# 48-17V_Buck_Converter.net
KiCad netlist of a schematic drawn in Altium Designer
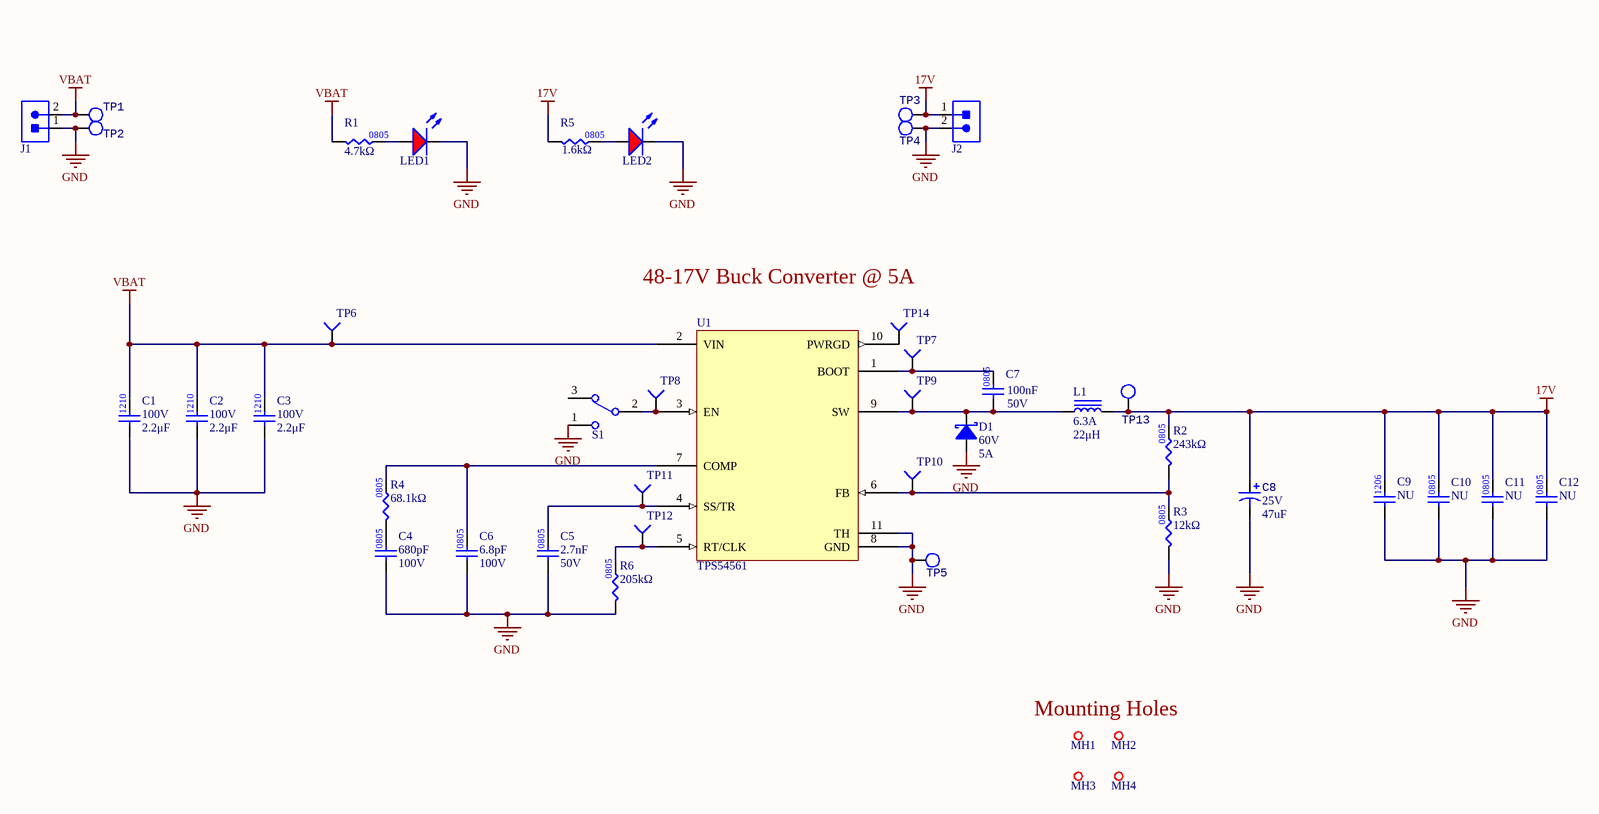
[diagram p0: 48-17V Buck Converter.SchDoc]

(export (version "E")
  (design (tool "Eeschema 10.0.6"))
  (components
    (comp (ref "C1")
      (value "2.2μF")
      (footprint "CAPC3225X270N")
      (description "CAP CER 2.2UF 100V X7R 1210")
      (fields (field (name "VOLTAGE RATING") "100V") (field (name "Comment") "CAP_2.2uF_100V_1210_1"))
      (libsource (lib "UWRT_Schematic_Library_2020") (part "CAP_2.2uF_100V_1210_1"))
    )
    (comp (ref "C2")
      (value "2.2μF")
      (footprint "CAPC3225X270N")
      (description "CAP CER 2.2UF 100V X7R 1210")
      (fields (field (name "VOLTAGE RATING") "100V") (field (name "Comment") "CAP_2.2uF_100V_1210_1"))
      (libsource (lib "UWRT_Schematic_Library_2020") (part "CAP_2.2uF_100V_1210_1"))
    )
    (comp (ref "C3")
      (value "2.2μF")
      (footprint "CAPC3225X270N")
      (description "CAP CER 2.2UF 100V X7R 1210")
      (fields (field (name "VOLTAGE RATING") "100V") (field (name "Comment") "CAP_2.2uF_100V_1210_1"))
      (libsource (lib "UWRT_Schematic_Library_2020") (part "CAP_2.2uF_100V_1210_1"))
    )
    (comp (ref "C4")
      (value "680pF")
      (footprint "CAP0805")
      (description "CAP CER 680PF 100V C0G/NP0 0805")
      (fields (field (name "VOLTAGE RATING") "100V") (field (name "Comment") "CAP_680pF_50V_0805"))
      (libsource (lib "UWRT_Schematic_Library_2020") (part "CAP_680pF_50V_0805"))
    )
    (comp (ref "C5")
      (value "2.7nF")
      (footprint "CAP0805")
      (description "CAP CER 2700PF 50V C0G 0805")
      (fields (field (name "VOLTAGE RATING") "50V") (field (name "Comment") "CAP_2.7nF_50V_0805"))
      (libsource (lib "UWRT_Schematic_Library_2020") (part "CAP_2.7nF_50V_0805"))
    )
    (comp (ref "C6")
      (value "6.8pF")
      (footprint "CAP0805")
      (description "CAP CER 6.8PF 100V C0G/NP0 0805")
      (fields (field (name "VOLTAGE RATING") "100V") (field (name "Comment") "CAP_6.8pF_100V_0805"))
      (libsource (lib "UWRT_Schematic_Library_2020") (part "CAP_6.8pF_100V_0805"))
    )
    (comp (ref "C7")
      (value "100nF")
      (footprint "CAP0805")
      (description "CAP CER 0.1UF 50V X7R 0805")
      (fields (field (name "VOLTAGE RATING") "50V") (field (name "Comment") "CAP_100nF_50V_0805"))
      (libsource (lib "UWRT_Schematic_Library_2020") (part "CAP_100nF_50V_0805"))
    )
    (comp (ref "C8")
      (value "47uF")
      (footprint "CAP_47uF_25V_ALUM")
      (description "CAP ALUM POLY 47UF 20% 25V SMD")
      (fields (field (name "VOLTAGE") "25V") (field (name "Comment") "CAP_47uF_25V_ALUM"))
      (libsource (lib "UWRT_Schematic_Library_2020") (part "CAP_47uF_25V_ALUM"))
    )
    (comp (ref "C9")
      (value "NU")
      (footprint "CAP1206")
      (description "PLACEHOLDER CAPACITOR")
      (fields (field (name "Comment") "CAP_NU_1206"))
      (libsource (lib "UWRT_Schematic_Library_2020") (part "CAP_NU_1206"))
    )
    (comp (ref "C10")
      (value "NU")
      (footprint "CAP0805")
      (description "PLACEHOLDER CAPACITOR")
      (fields (field (name "Comment") "CAP_NU_0805"))
      (libsource (lib "UWRT_Schematic_Library_2020") (part "CAP_NU_0805"))
    )
    (comp (ref "C11")
      (value "NU")
      (footprint "CAP0805")
      (description "PLACEHOLDER CAPACITOR")
      (fields (field (name "Comment") "CAP_NU_0805"))
      (libsource (lib "UWRT_Schematic_Library_2020") (part "CAP_NU_0805"))
    )
    (comp (ref "C12")
      (value "NU")
      (footprint "CAP0805")
      (description "PLACEHOLDER CAPACITOR")
      (fields (field (name "Comment") "CAP_NU_0805"))
      (libsource (lib "UWRT_Schematic_Library_2020") (part "CAP_NU_0805"))
    )
    (comp (ref "D1")
      (value "DIO_SCHOTTKY_30V_800mA")
      (footprint "SOD-323_UNIDIR")
      (description "DIODE SCHOTTKY 60V 5A SMC")
      (fields (field (name "VR (MAX)") "60V") (field (name "IO") "5A"))
      (libsource (lib "UWRT_Schematic_Library_2020") (part "DIO_SCHOTTKY_60V_5A"))
    )
    (comp (ref "J1")
      (value "CON_2POS_SCREW_TERM")
      (footprint "1935161")
      (description "TERM BLK 2POS SIDE ENTRY 5MM")
      (libsource (lib "") (part "CON_2POS_SCREW_TERM_1"))
    )
    (comp (ref "J2")
      (value "CON_2POS_SCREW_TERM")
      (footprint "1935161")
      (description "TERM BLK 2POS SIDE ENTRY 5MM")
      (libsource (lib "UWRT_Schematic_Library_2020") (part "CON_2POS_SCREW_TERM"))
    )
    (comp (ref "L1")
      (value "IND_22uH_6.3A")
      (footprint "UWRT_Footprint_Library_2020:IND_22uH_6.3A")
      (description "FIXED IND 22UH 6.3A 25.7MOHM SMD")
      (fields (field (name "CURRENT RATING") "6.3A") (field (name "INDUCTANCE") "22μH"))
      (libsource (lib "UWRT_Schematic_Library_2020") (part "IND_22uH_6.3A"))
    )
    (comp (ref "LED1")
      (value "LED_RED")
      (footprint "LED_0805_RED")
      (description "LED RED DIFFUSED 0805 SMD")
      (libsource (lib "UWRT_Schematic_Library_2020") (part "LED_RED"))
    )
    (comp (ref "LED2")
      (value "LED_RED")
      (footprint "LED_0805_RED")
      (description "LED RED DIFFUSED 0805 SMD")
      (libsource (lib "UWRT_Schematic_Library_2020") (part "LED_RED"))
    )
    (comp (ref "MH1")
      (value "MOUNTING_HOLE_M3_GIMBAL_REV2")
      (footprint "MOUNTING_HOLE_3mm_GIMBAL_REV2")
      (description "MOUNTING_HOLE_M3 Gimbal Rev2")
      (libsource (lib "UWRT_Schematic_Library_2020") (part "MOUNTING_HOLE_M3_GIMBAL_REV2"))
    )
    (comp (ref "MH2")
      (value "MOUNTING_HOLE_M3_GIMBAL_REV2")
      (footprint "MOUNTING_HOLE_3mm_GIMBAL_REV2")
      (description "MOUNTING_HOLE_M3 Gimbal Rev2")
      (libsource (lib "UWRT_Schematic_Library_2020") (part "MOUNTING_HOLE_M3_GIMBAL_REV2"))
    )
    (comp (ref "MH3")
      (value "MOUNTING_HOLE_M3_GIMBAL_REV2")
      (footprint "MOUNTING_HOLE_3mm_GIMBAL_REV2")
      (description "MOUNTING_HOLE_M3 Gimbal Rev2")
      (libsource (lib "UWRT_Schematic_Library_2020") (part "MOUNTING_HOLE_M3_GIMBAL_REV2"))
    )
    (comp (ref "MH4")
      (value "MOUNTING_HOLE_M3_GIMBAL_REV2")
      (footprint "MOUNTING_HOLE_3mm_GIMBAL_REV2")
      (description "MOUNTING_HOLE_M3 Gimbal Rev2")
      (libsource (lib "UWRT_Schematic_Library_2020") (part "MOUNTING_HOLE_M3_GIMBAL_REV2"))
    )
    (comp (ref "R1")
      (value "4.7kΩ")
      (footprint "RES0805")
      (description "RES 4.7K OHM 5% 1/8W 0805")
      (fields (field (name "LCSC PART #") "C17673") (field (name "Comment") "RES_4.7kΩ_0805_5%"))
      (libsource (lib "UWRT_Schematic_Library_2020") (part "RES_4.7kΩ_0805_5%"))
    )
    (comp (ref "R2")
      (value "243kΩ")
      (footprint "RES0805")
      (description "RES 243K OHM 1% 1/8W 0805")
      (fields (field (name "Comment") "RES_243kΩ_0805_1%_1"))
      (libsource (lib "UWRT_Schematic_Library_2020") (part "RES_243kΩ_0805_1%_1"))
    )
    (comp (ref "R3")
      (value "12kΩ")
      (footprint "RES0805")
      (description "RES 12K OHM 1% 1/8W 0805")
      (fields (field (name "Comment") "RES_12kΩ_0805_1%"))
      (libsource (lib "UWRT_Schematic_Library_2020") (part "RES_12kΩ_0805_1%"))
    )
    (comp (ref "R4")
      (value "68.1kΩ")
      (footprint "RES0805")
      (description "RES 68.1K OHM 1% 1/8W 0805")
      (fields (field (name "Comment") "RES_68.1kΩ_0805_1%"))
      (libsource (lib "UWRT_Schematic_Library_2020") (part "RES_68.1kΩ_0805_1%"))
    )
    (comp (ref "R5")
      (value "1.6kΩ")
      (footprint "RES0805")
      (description "RES 1.6K OHM 0.1% 1/4W 0805")
      (fields (field (name "TOLERANCE") "0.1%") (field (name "Comment") "RES_1.6kΩ_0805_0.1%"))
      (libsource (lib "UWRT_Schematic_Library_2020") (part "RES_1.6kΩ_0805_0.1%"))
    )
    (comp (ref "R6")
      (value "205kΩ")
      (footprint "RES0805")
      (description "RES 205K OHM 1% 1/8W 0805")
      (fields (field (name "Comment") "RES_205kΩ_0805_1%"))
      (libsource (lib "UWRT_Schematic_Library_2020") (part "RES_205kΩ_0805_1%"))
    )
    (comp (ref "S1")
      (value "SW_SLIDE_TOGGLE")
      (footprint "UWRT_Footprint_Library_2020:SW_SLIDE_TOGGLE")
      (description "SWITCH SLIDE SPDT 200MA 30V")
      (libsource (lib "UWRT_Schematic_Library_2020") (part "SW_SLIDE_TOGGLE"))
    )
    (comp (ref "TP1")
      (value "TESTPOINT_LOOP")
      (footprint "TESTPOINT_LOOP")
      (description "TESTPOINT THRUHOLE")
      (libsource (lib "UWRT_Schematic_Library_2020") (part "TESTPOINT_LOOP"))
    )
    (comp (ref "TP2")
      (value "TESTPOINT_LOOP")
      (footprint "TESTPOINT_LOOP")
      (description "TESTPOINT THRUHOLE")
      (libsource (lib "UWRT_Schematic_Library_2020") (part "TESTPOINT_LOOP"))
    )
    (comp (ref "TP3")
      (value "TESTPOINT_LOOP")
      (footprint "TESTPOINT_LOOP")
      (description "TESTPOINT THRUHOLE")
      (libsource (lib "UWRT_Schematic_Library_2020") (part "TESTPOINT_LOOP"))
    )
    (comp (ref "TP4")
      (value "TESTPOINT_LOOP")
      (footprint "TESTPOINT_LOOP")
      (description "TESTPOINT THRUHOLE")
      (libsource (lib "UWRT_Schematic_Library_2020") (part "TESTPOINT_LOOP"))
    )
    (comp (ref "TP5")
      (value "TESTPOINT_LOOP")
      (footprint "TESTPOINT_LOOP")
      (description "TESTPOINT THRUHOLE")
      (libsource (lib "UWRT_Schematic_Library_2020") (part "TESTPOINT_LOOP"))
    )
    (comp (ref "TP6")
      (value "TESTPOINT_1MM_CIRCLE")
      (footprint "TESTPOINT_CIRCLE_1MM")
      (description "TESTPOINT 1MM CIRCLE")
      (libsource (lib "UWRT_Schematic_Library_2020") (part "TESTPOINT_1MM_CIRCLE"))
    )
    (comp (ref "TP7")
      (value "TESTPOINT_1MM_CIRCLE")
      (footprint "TESTPOINT_CIRCLE_1MM")
      (description "TESTPOINT 1MM CIRCLE")
      (libsource (lib "UWRT_Schematic_Library_2020") (part "TESTPOINT_1MM_CIRCLE"))
    )
    (comp (ref "TP8")
      (value "TESTPOINT_1MM_CIRCLE")
      (footprint "TESTPOINT_CIRCLE_1MM")
      (description "TESTPOINT 1MM CIRCLE")
      (libsource (lib "UWRT_Schematic_Library_2020") (part "TESTPOINT_1MM_CIRCLE"))
    )
    (comp (ref "TP9")
      (value "TESTPOINT_1MM_CIRCLE")
      (footprint "TESTPOINT_CIRCLE_1MM")
      (description "TESTPOINT 1MM CIRCLE")
      (libsource (lib "UWRT_Schematic_Library_2020") (part "TESTPOINT_1MM_CIRCLE"))
    )
    (comp (ref "TP10")
      (value "TESTPOINT_1MM_CIRCLE")
      (footprint "TESTPOINT_CIRCLE_1MM")
      (description "TESTPOINT 1MM CIRCLE")
      (libsource (lib "UWRT_Schematic_Library_2020") (part "TESTPOINT_1MM_CIRCLE"))
    )
    (comp (ref "TP11")
      (value "TESTPOINT_1MM_CIRCLE")
      (footprint "TESTPOINT_CIRCLE_1MM")
      (description "TESTPOINT 1MM CIRCLE")
      (libsource (lib "UWRT_Schematic_Library_2020") (part "TESTPOINT_1MM_CIRCLE"))
    )
    (comp (ref "TP12")
      (value "TESTPOINT_1MM_CIRCLE")
      (footprint "TESTPOINT_CIRCLE_1MM")
      (description "TESTPOINT 1MM CIRCLE")
      (libsource (lib "UWRT_Schematic_Library_2020") (part "TESTPOINT_1MM_CIRCLE"))
    )
    (comp (ref "TP13")
      (value "TESTPOINT_LOOP")
      (footprint "TESTPOINT_LOOP")
      (description "TESTPOINT THRUHOLE")
      (libsource (lib "UWRT_Schematic_Library_2020") (part "TESTPOINT_LOOP"))
    )
    (comp (ref "TP14")
      (value "TESTPOINT_1MM_CIRCLE")
      (footprint "TESTPOINT_CIRCLE_1MM")
      (description "TESTPOINT 1MM CIRCLE")
      (libsource (lib "UWRT_Schematic_Library_2020") (part "TESTPOINT_1MM_CIRCLE"))
    )
    (comp (ref "U1")
      (value "TPS54561")
      (footprint "BUCK_TPS54561DPRR")
      (description "Buck Switching Regulator IC Positive Adjustable 0.8V 1 Output 5A 10-WDFN Exposed Pad")
      (libsource (lib "UWRT_Schematic_Library_2020") (part "TPS54561"))
    )
  )
  (nets
    (net (code "1") (name "17V") (class "Default")
      (node (ref "C10") (pin "2") (pinfunction "2_2") (pintype "passive"))
      (node (ref "C11") (pin "2") (pinfunction "2_2") (pintype "passive"))
      (node (ref "C12") (pin "2") (pinfunction "2_2") (pintype "passive"))
      (node (ref "C8") (pin "1") (pinfunction "1_1") (pintype "passive"))
      (node (ref "C9") (pin "2") (pinfunction "2_2") (pintype "passive"))
      (node (ref "J2") (pin "1") (pinfunction "1_1") (pintype "passive"))
      (node (ref "L1") (pin "2") (pinfunction "2_2") (pintype "passive"))
      (node (ref "R2") (pin "2") (pinfunction "2_2") (pintype "passive"))
      (node (ref "R5") (pin "1") (pinfunction "1_1") (pintype "passive"))
      (node (ref "TP13") (pin "1") (pintype "passive"))
      (node (ref "TP3") (pin "1") (pintype "passive"))
    )
    (net (code "2") (name "GND") (class "Default")
      (node (ref "C1") (pin "1") (pinfunction "1_1") (pintype "passive"))
      (node (ref "C10") (pin "1") (pinfunction "1_1") (pintype "passive"))
      (node (ref "C11") (pin "1") (pinfunction "1_1") (pintype "passive"))
      (node (ref "C12") (pin "1") (pinfunction "1_1") (pintype "passive"))
      (node (ref "C2") (pin "1") (pinfunction "1_1") (pintype "passive"))
      (node (ref "C3") (pin "1") (pinfunction "1_1") (pintype "passive"))
      (node (ref "C4") (pin "1") (pinfunction "1_1") (pintype "passive"))
      (node (ref "C5") (pin "1") (pinfunction "1_1") (pintype "passive"))
      (node (ref "C6") (pin "1") (pinfunction "1_1") (pintype "passive"))
      (node (ref "C8") (pin "2") (pinfunction "2_2") (pintype "passive"))
      (node (ref "C9") (pin "1") (pinfunction "1_1") (pintype "passive"))
      (node (ref "D1") (pin "1") (pinfunction "Anode_1") (pintype "passive"))
      (node (ref "J1") (pin "1") (pinfunction "1_1") (pintype "passive"))
      (node (ref "J2") (pin "2") (pinfunction "2_2") (pintype "passive"))
      (node (ref "LED1") (pin "2") (pinfunction "K_2") (pintype "passive"))
      (node (ref "LED2") (pin "2") (pinfunction "K_2") (pintype "passive"))
      (node (ref "R3") (pin "1") (pinfunction "1_1") (pintype "passive"))
      (node (ref "R6") (pin "1") (pinfunction "1_1") (pintype "passive"))
      (node (ref "S1") (pin "1") (pinfunction "1_1") (pintype "passive"))
      (node (ref "TP2") (pin "1") (pintype "passive"))
      (node (ref "TP4") (pin "1") (pintype "passive"))
      (node (ref "TP5") (pin "1") (pintype "passive"))
      (node (ref "U1") (pin "11") (pinfunction "TH_11") (pintype "power_in"))
      (node (ref "U1") (pin "8") (pinfunction "GND_8") (pintype "power_in"))
    )
    (net (code "3") (name "Net-(C4-Pad2)") (class "Default")
      (node (ref "C4") (pin "2") (pinfunction "2_2") (pintype "passive"))
      (node (ref "R4") (pin "1") (pinfunction "1_1") (pintype "passive"))
    )
    (net (code "4") (name "Net-(D1-Cathode)") (class "Default")
      (node (ref "C7") (pin "1") (pinfunction "1_1") (pintype "passive"))
      (node (ref "D1") (pin "2") (pinfunction "Cathode_2") (pintype "passive"))
      (node (ref "L1") (pin "1") (pinfunction "1_1") (pintype "passive"))
      (node (ref "TP9") (pin "1") (pinfunction "=value_1") (pintype "passive"))
      (node (ref "U1") (pin "9") (pinfunction "SW_9") (pintype "power_in"))
    )
    (net (code "5") (name "Net-(LED1-A)") (class "Default")
      (node (ref "LED1") (pin "1") (pinfunction "A_1") (pintype "passive"))
      (node (ref "R1") (pin "2") (pinfunction "2_2") (pintype "passive"))
    )
    (net (code "6") (name "Net-(LED2-A)") (class "Default")
      (node (ref "LED2") (pin "1") (pinfunction "A_1") (pintype "passive"))
      (node (ref "R5") (pin "2") (pinfunction "2_2") (pintype "passive"))
    )
    (net (code "7") (name "Net-(TP7-=value)") (class "Default")
      (node (ref "C7") (pin "2") (pinfunction "2_2") (pintype "passive"))
      (node (ref "TP7") (pin "1") (pinfunction "=value_1") (pintype "passive"))
      (node (ref "U1") (pin "1") (pinfunction "BOOT_1") (pintype "power_in"))
    )
    (net (code "8") (name "Net-(TP8-=value)") (class "Default")
      (node (ref "S1") (pin "2") (pinfunction "2_2") (pintype "passive"))
      (node (ref "TP8") (pin "1") (pinfunction "=value_1") (pintype "passive"))
      (node (ref "U1") (pin "3") (pinfunction "EN_3") (pintype "input"))
    )
    (net (code "9") (name "Net-(TP10-=value)") (class "Default")
      (node (ref "R2") (pin "1") (pinfunction "1_1") (pintype "passive"))
      (node (ref "R3") (pin "2") (pinfunction "2_2") (pintype "passive"))
      (node (ref "TP10") (pin "1") (pinfunction "=value_1") (pintype "passive"))
      (node (ref "U1") (pin "6") (pinfunction "FB_6") (pintype "input"))
    )
    (net (code "10") (name "Net-(TP11-=value)") (class "Default")
      (node (ref "C5") (pin "2") (pinfunction "2_2") (pintype "passive"))
      (node (ref "TP11") (pin "1") (pinfunction "=value_1") (pintype "passive"))
      (node (ref "U1") (pin "4") (pinfunction "SS/TR_4") (pintype "input"))
    )
    (net (code "11") (name "Net-(TP12-=value)") (class "Default")
      (node (ref "R6") (pin "2") (pinfunction "2_2") (pintype "passive"))
      (node (ref "TP12") (pin "1") (pinfunction "=value_1") (pintype "passive"))
      (node (ref "U1") (pin "5") (pinfunction "RT/CLK_5") (pintype "input"))
    )
    (net (code "12") (name "Net-(TP14-=value)") (class "Default")
      (node (ref "TP14") (pin "1") (pinfunction "=value_1") (pintype "passive"))
      (node (ref "U1") (pin "10") (pinfunction "PWRGD_10") (pintype "output"))
    )
    (net (code "13") (name "Net-(U1-COMP)") (class "Default")
      (node (ref "C6") (pin "2") (pinfunction "2_2") (pintype "passive"))
      (node (ref "R4") (pin "2") (pinfunction "2_2") (pintype "passive"))
      (node (ref "U1") (pin "7") (pinfunction "COMP_7") (pintype "power_in"))
    )
    (net (code "14") (name "VBAT") (class "Default")
      (node (ref "C1") (pin "2") (pinfunction "2_2") (pintype "passive"))
      (node (ref "C2") (pin "2") (pinfunction "2_2") (pintype "passive"))
      (node (ref "C3") (pin "2") (pinfunction "2_2") (pintype "passive"))
      (node (ref "J1") (pin "2") (pinfunction "2_2") (pintype "passive"))
      (node (ref "R1") (pin "1") (pinfunction "1_1") (pintype "passive"))
      (node (ref "TP1") (pin "1") (pintype "passive"))
      (node (ref "TP6") (pin "1") (pinfunction "=value_1") (pintype "passive"))
      (node (ref "U1") (pin "2") (pinfunction "VIN_2") (pintype "power_in"))
    )
    (net (code "15") (name "unconnected-(S1-Pad3)") (class "Default")
      (node (ref "S1") (pin "3") (pinfunction "3_3") (pintype "passive"))
    )
  )
)
